# linear_power_supply.net
KiCad netlist of a schematic drawn in Altium Designer
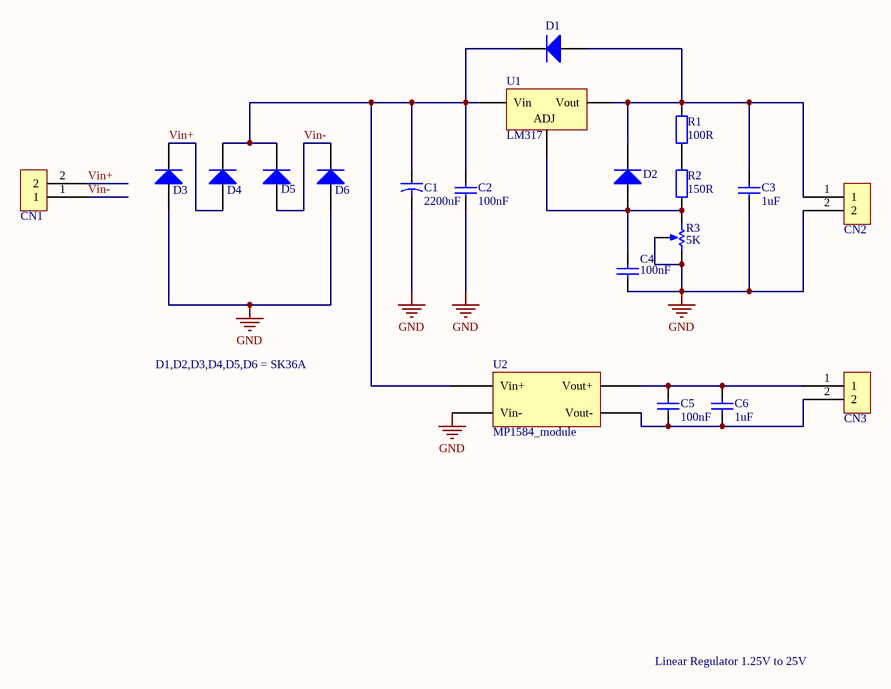
[diagram p0: linear_power_supply.SchDoc]

(export (version "E")
  (design (tool "Eeschema 10.0.6"))
  (components
    (comp (ref "C1")
      (value "2200uF")
      (footprint "CAPR5-4X5")
      (description "Capacitor")
      (fields (field (name "Comment") "Cap2") (field (name "PUBLISHER") "Altium Limited"))
      (libsource (lib "Miscellaneous Devices") (part "Cap2"))
    )
    (comp (ref "C2")
      (value "100nF")
      (footprint "0805 C")
      (description "Capacitor, ceramic, 100nF, 50V, 0805")
      (fields
        (field (name "PART NUMBER") "RK-cer-100nF-50V-0805")
        (field (name "Comment") "Cap-cer-100nF-50V-0805")
      )
      (libsource (lib "RAKS") (part "Cap-cer-100nF-50V-0805"))
    )
    (comp (ref "C3")
      (value "1uF")
      (footprint "0805 C")
      (description "Capacitor, ceramic, 1uF, 16V, 0805")
      (fields
        (field (name "PART NUMBER") "RK-cer-1uF-16V-0805")
        (field (name "Comment") "Cap-cer-1uF-16V-0805")
      )
      (libsource (lib "RAKS") (part "Cap-cer-1uF-16V-0805"))
    )
    (comp (ref "C4")
      (value "100nF")
      (footprint "0805 C")
      (description "Capacitor, ceramic, 100nF, 50V, 0805")
      (fields
        (field (name "PART NUMBER") "RK-cer-100nF-50V-0805")
        (field (name "Comment") "Cap-cer-100nF-50V-0805")
      )
      (libsource (lib "RAKS") (part "Cap-cer-100nF-50V-0805"))
    )
    (comp (ref "C5")
      (value "100nF")
      (footprint "0805 C")
      (description "Capacitor, ceramic, 100nF, 50V, 0805")
      (fields
        (field (name "PART NUMBER") "RK-cer-100nF-50V-0805")
        (field (name "Comment") "Cap-cer-100nF-50V-0805")
      )
      (libsource (lib "RAKS") (part "Cap-cer-100nF-50V-0805"))
    )
    (comp (ref "C6")
      (value "1uF")
      (footprint "0805 C")
      (description "Capacitor, ceramic, 1uF, 16V, 0805")
      (fields
        (field (name "PART NUMBER") "RK-cer-1uF-16V-0805")
        (field (name "Comment") "Cap-cer-1uF-16V-0805")
      )
      (libsource (lib "RAKS") (part "Cap-cer-1uF-16V-0805"))
    )
    (comp (ref "CN1")
      (value "Pin Head 2")
      (footprint "KRM mini")
      (libsource (lib "RAKS") (part "Pin Head 2"))
    )
    (comp (ref "CN2") (value "Pin Head 2") (footprint "KRM mini") (libsource (lib "") (part "Pin Head 2_1")))
    (comp (ref "CN3") (value "Pin Head 2") (footprint "KRM mini") (libsource (lib "") (part "Pin Head 2_1")))
    (comp (ref "D1")
      (value "Diode 1N4007")
      (footprint "DO-214AC")
      (description "1 Amp General Purpose Rectifier")
      (fields (field (name "PUBLISHER") "Altium Limited"))
      (libsource (lib "RAKS") (part "Diode 1N4007"))
    )
    (comp (ref "D2")
      (value "Diode 1N4007")
      (footprint "DO-214AC")
      (description "1 Amp General Purpose Rectifier")
      (fields (field (name "PUBLISHER") "Altium Limited"))
      (libsource (lib "RAKS") (part "Diode 1N4007"))
    )
    (comp (ref "D3")
      (value "Diode 1N4007")
      (footprint "DO-214AC")
      (description "1 Amp General Purpose Rectifier")
      (fields (field (name "PUBLISHER") "Altium Limited"))
      (libsource (lib "RAKS") (part "Diode 1N4007"))
    )
    (comp (ref "D4")
      (value "Diode 1N4007")
      (footprint "DO-214AC")
      (description "1 Amp General Purpose Rectifier")
      (fields (field (name "PUBLISHER") "Altium Limited"))
      (libsource (lib "RAKS") (part "Diode 1N4007"))
    )
    (comp (ref "D5")
      (value "Diode 1N4007")
      (footprint "DO-214AC")
      (description "1 Amp General Purpose Rectifier")
      (fields (field (name "PUBLISHER") "Altium Limited"))
      (libsource (lib "RAKS") (part "Diode 1N4007"))
    )
    (comp (ref "D6")
      (value "Diode 1N4007")
      (footprint "DO-214AC")
      (description "1 Amp General Purpose Rectifier")
      (fields (field (name "PUBLISHER") "Altium Limited"))
      (libsource (lib "RAKS") (part "Diode 1N4007"))
    )
    (comp (ref "R1")
      (value "100R")
      (footprint "0805 R")
      (description "Resistor, 100R, 0805, 1%, 1/8W")
      (fields
        (field (name "PART NUMBER") "RK-100R-0805-1%-1/8W")
        (field (name "Comment") "Res-100R-0805-1%-1/8W")
      )
      (libsource (lib "RAKS") (part "Res-100R-0805-1%-1/8W"))
    )
    (comp (ref "R2")
      (value "150R")
      (footprint "0805 R")
      (description "Resistor, 150R, 0805, 1%, 1/8W")
      (fields
        (field (name "PART NUMBER") "RK-150R-0805-1%-1/8W")
        (field (name "Comment") "Res-150R-0805-1%-1/8W")
      )
      (libsource (lib "RAKS") (part "Res-150R-0805-1%-1/8W"))
    )
    (comp (ref "R3")
      (value "5K")
      (footprint "VR5")
      (description "Potentiometer")
      (fields (field (name "Comment") "RPot") (field (name "PUBLISHER") "Altium Limited"))
      (libsource (lib "Miscellaneous Devices") (part "RPot"))
    )
    (comp (ref "U1")
      (value "LM317")
      (footprint "DPAK")
      (description "Linear Voltage Regulator")
      (fields (field (name "PUBLISHER") "Altium Limited"))
      (libsource (lib "RAKS") (part "LM317"))
    )
    (comp (ref "U2")
      (value "MP1584_module")
      (footprint "MP1584_module")
      (description "Buck regulator module")
      (libsource (lib "RAKS") (part "MP1584_module"))
    )
  )
  (nets
    (net (code "1") (name "/Vin+") (class "Default")
      (node (ref "CN1") (pin "2") (pinfunction "2_2") (pintype "passive"))
      (node (ref "D3") (pin "2") (pinfunction "K_2") (pintype "passive"))
      (node (ref "D4") (pin "1") (pinfunction "A_1") (pintype "passive"))
    )
    (net (code "2") (name "/Vin-") (class "Default")
      (node (ref "CN1") (pin "1") (pinfunction "1_1") (pintype "passive"))
      (node (ref "D5") (pin "1") (pinfunction "A_1") (pintype "passive"))
      (node (ref "D6") (pin "2") (pinfunction "K_2") (pintype "passive"))
    )
    (net (code "3") (name "GND") (class "Default")
      (node (ref "C1") (pin "2") (pinfunction "2_2") (pintype "passive"))
      (node (ref "C2") (pin "1") (pinfunction "1_1") (pintype "passive"))
      (node (ref "C3") (pin "1") (pinfunction "1_1") (pintype "passive"))
      (node (ref "C4") (pin "1") (pinfunction "1_1") (pintype "passive"))
      (node (ref "CN2") (pin "2") (pinfunction "2_2") (pintype "passive"))
      (node (ref "D3") (pin "1") (pinfunction "A_1") (pintype "passive"))
      (node (ref "D6") (pin "1") (pinfunction "A_1") (pintype "passive"))
      (node (ref "R3") (pin "2") (pinfunction "BOT_2") (pintype "passive"))
      (node (ref "R3") (pin "3") (pinfunction "TAP_3") (pintype "passive"))
      (node (ref "U2") (pin "2") (pinfunction "Vin-_2") (pintype "passive"))
    )
    (net (code "4") (name "Net-(D1-A)") (class "Default")
      (node (ref "C3") (pin "2") (pinfunction "2_2") (pintype "passive"))
      (node (ref "CN2") (pin "1") (pinfunction "1_1") (pintype "passive"))
      (node (ref "D1") (pin "1") (pinfunction "A_1") (pintype "passive"))
      (node (ref "D2") (pin "2") (pinfunction "K_2") (pintype "passive"))
      (node (ref "R1") (pin "2") (pinfunction "2_2") (pintype "passive"))
      (node (ref "U1") (pin "3") (pinfunction "Vout_3") (pintype "passive"))
    )
    (net (code "5") (name "Net-(D1-K)") (class "Default")
      (node (ref "C1") (pin "1") (pinfunction "1_1") (pintype "passive"))
      (node (ref "C2") (pin "2") (pinfunction "2_2") (pintype "passive"))
      (node (ref "D1") (pin "2") (pinfunction "K_2") (pintype "passive"))
      (node (ref "D4") (pin "2") (pinfunction "K_2") (pintype "passive"))
      (node (ref "D5") (pin "2") (pinfunction "K_2") (pintype "passive"))
      (node (ref "U1") (pin "2") (pinfunction "Vin_2") (pintype "passive"))
      (node (ref "U2") (pin "1") (pinfunction "Vin+_1") (pintype "passive"))
    )
    (net (code "6") (name "Net-(D2-A)") (class "Default")
      (node (ref "C4") (pin "2") (pinfunction "2_2") (pintype "passive"))
      (node (ref "D2") (pin "1") (pinfunction "A_1") (pintype "passive"))
      (node (ref "R2") (pin "1") (pinfunction "1_1") (pintype "passive"))
      (node (ref "R3") (pin "1") (pinfunction "TOP_1") (pintype "passive"))
      (node (ref "U1") (pin "1") (pinfunction "ADJ_1") (pintype "passive"))
    )
    (net (code "7") (name "Net-(R1-Pad1)") (class "Default")
      (node (ref "R1") (pin "1") (pinfunction "1_1") (pintype "passive"))
      (node (ref "R2") (pin "2") (pinfunction "2_2") (pintype "passive"))
    )
    (net (code "8") (name "Net-(U2-Vout+)") (class "Default")
      (node (ref "C5") (pin "2") (pinfunction "2_2") (pintype "passive"))
      (node (ref "C6") (pin "2") (pinfunction "2_2") (pintype "passive"))
      (node (ref "CN3") (pin "1") (pinfunction "1_1") (pintype "passive"))
      (node (ref "U2") (pin "4") (pinfunction "Vout+_4") (pintype "passive"))
    )
    (net (code "9") (name "Net-(U2-Vout-)") (class "Default")
      (node (ref "C5") (pin "1") (pinfunction "1_1") (pintype "passive"))
      (node (ref "C6") (pin "1") (pinfunction "1_1") (pintype "passive"))
      (node (ref "CN3") (pin "2") (pinfunction "2_2") (pintype "passive"))
      (node (ref "U2") (pin "3") (pinfunction "Vout-_3") (pintype "passive"))
    )
  )
)
